# easiri.net
KiCad netlist of a schematic drawn in EAGLE
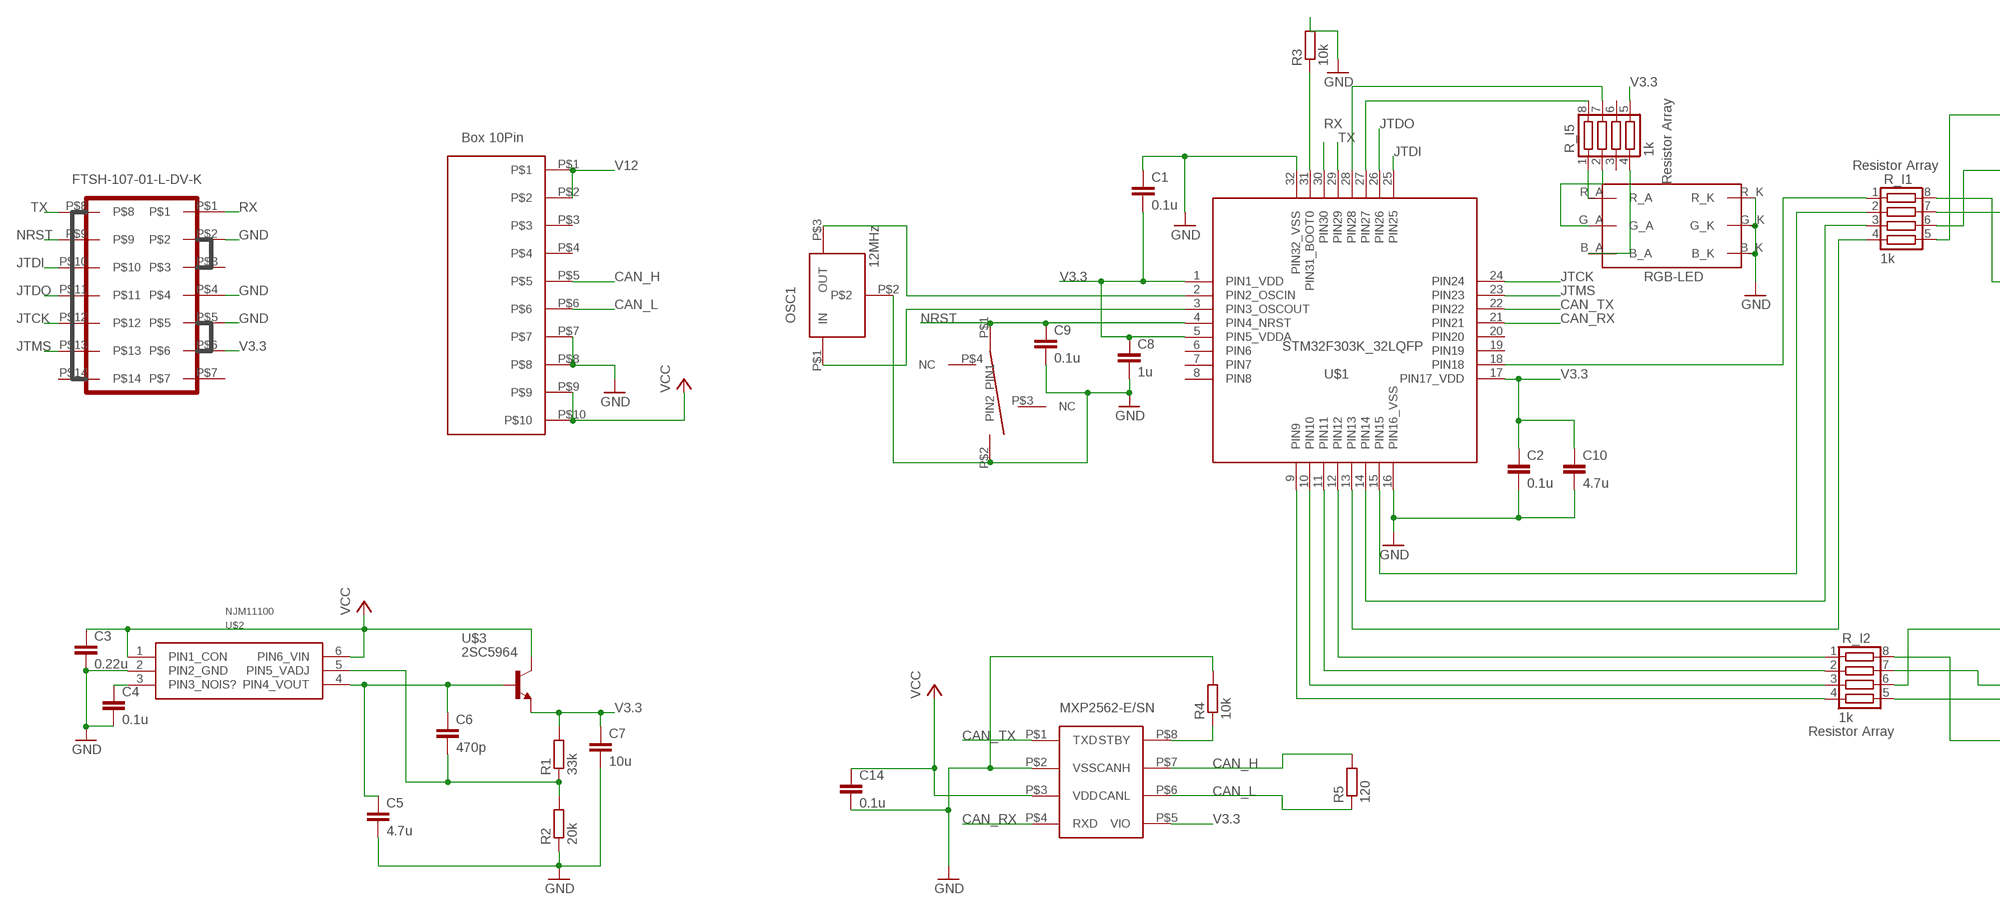
[diagram p0: schematic, sheet 1, part 1 of 2]
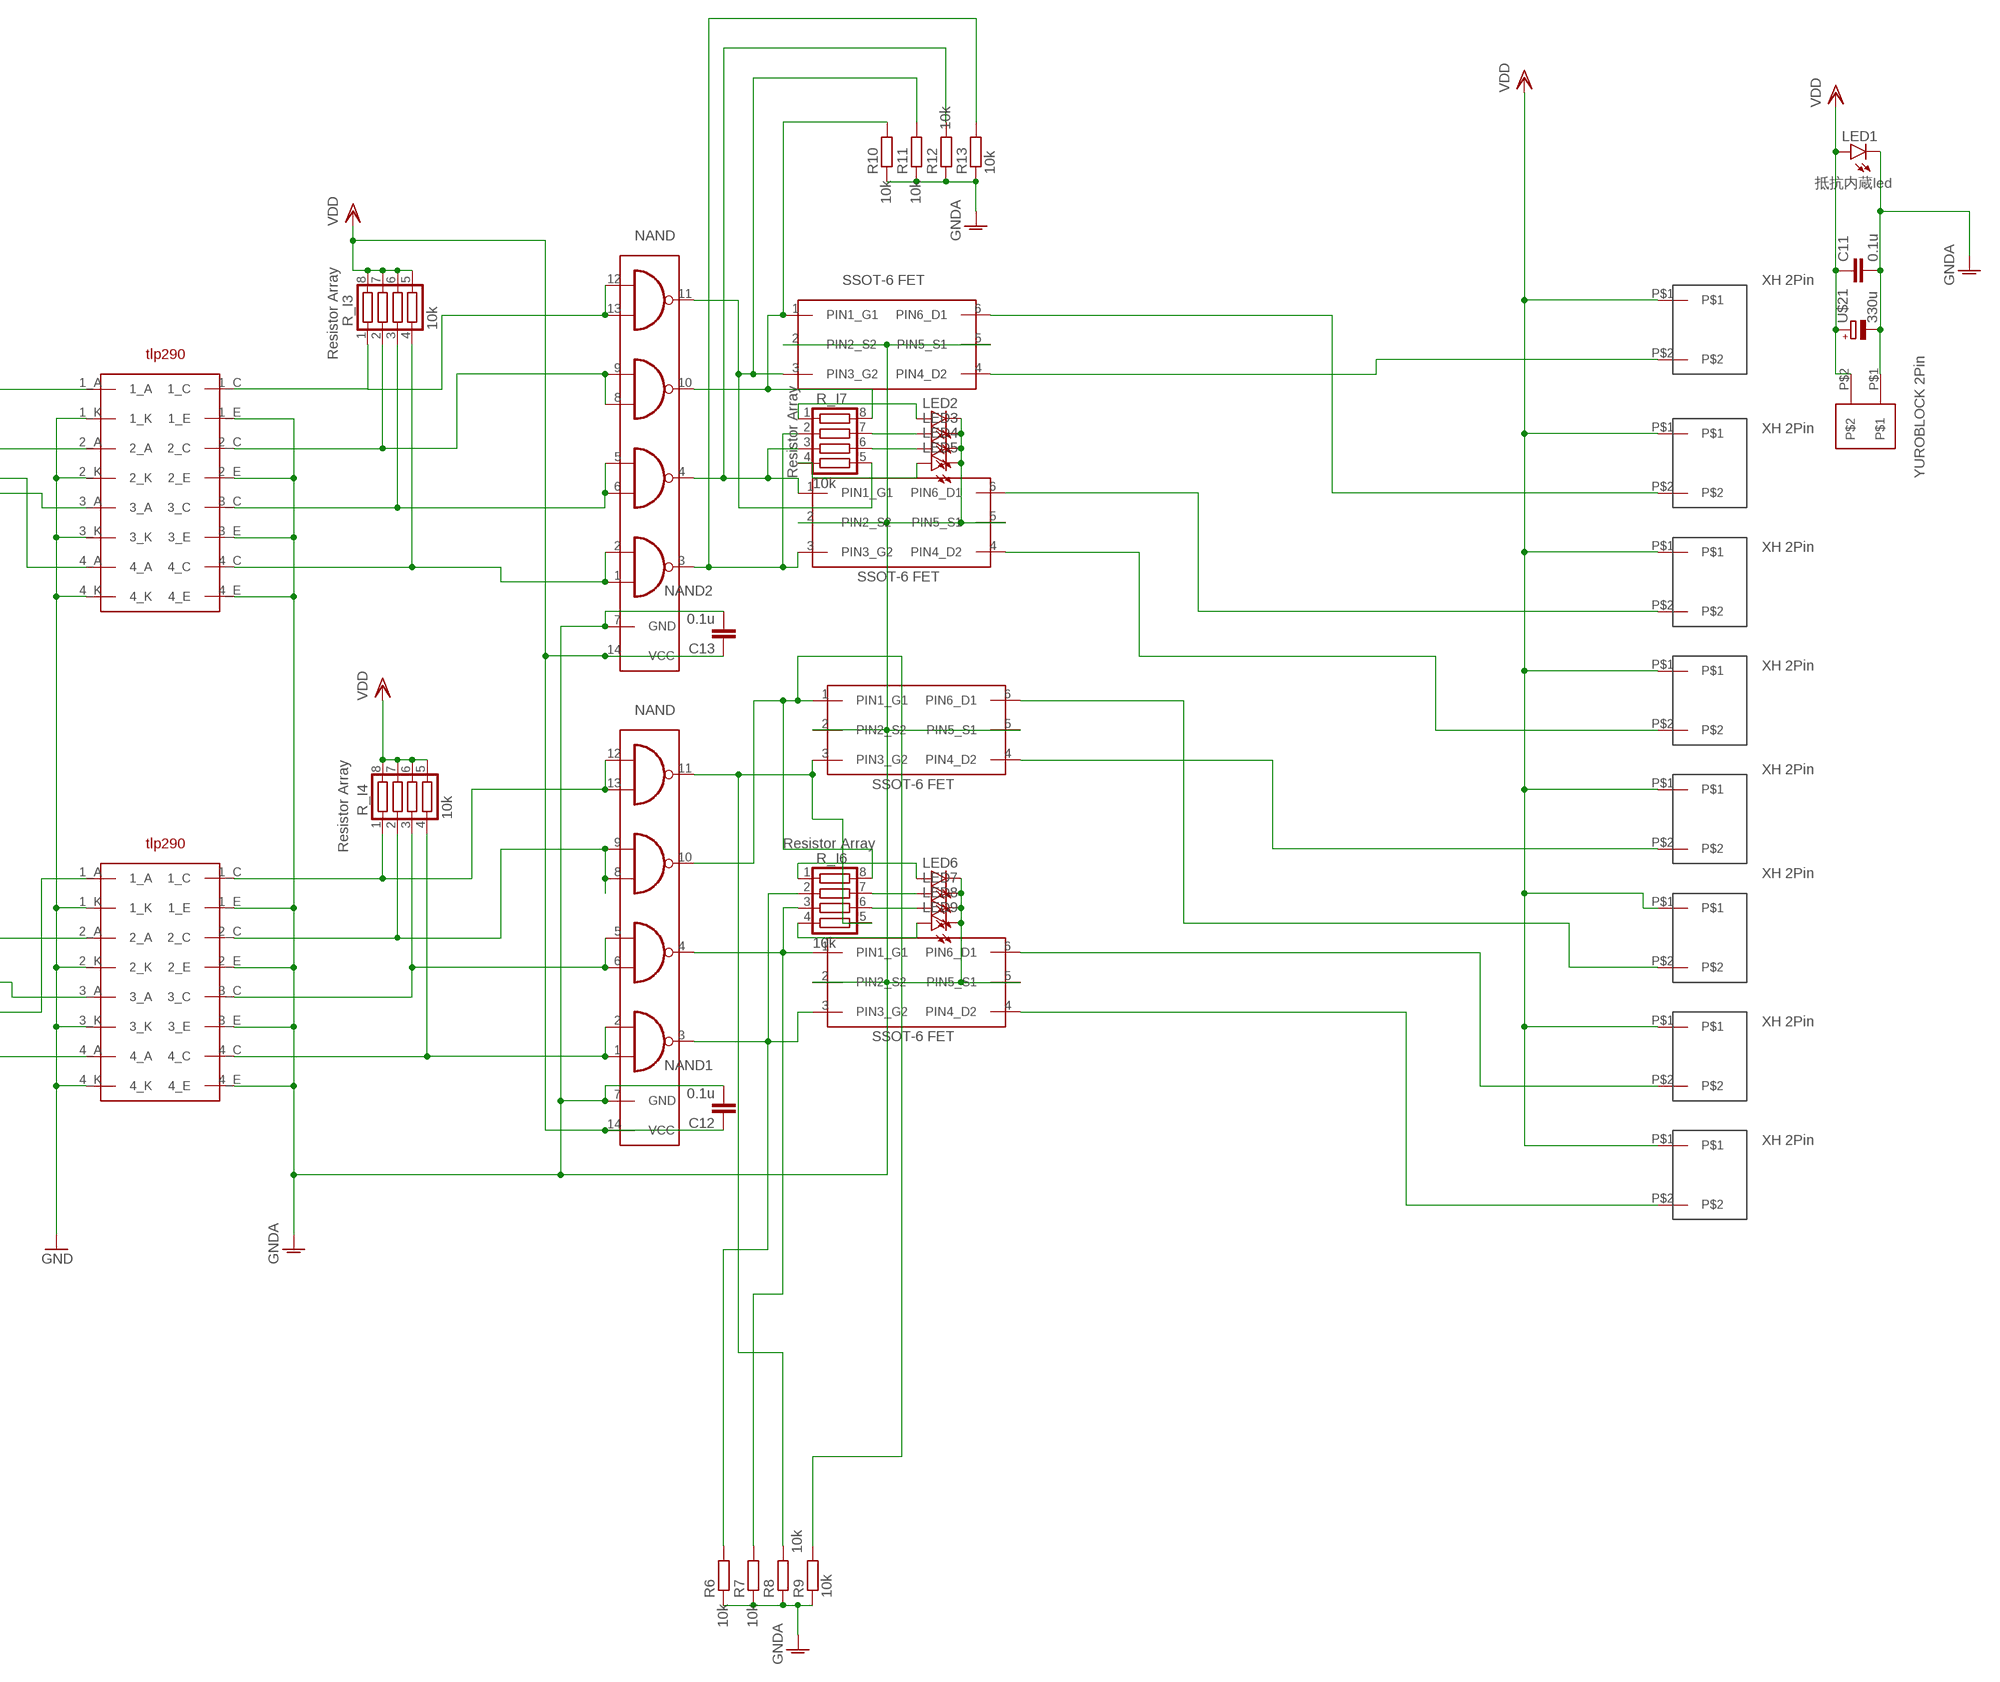
[diagram p1: schematic, sheet 1, part 2 of 2]

(export (version "E")
  (design (tool "Eeschema 10.0.6"))
  (components
    (comp (ref "BOX10P-L2")
      (value "BOX10PBOX10P-L")
      (footprint "eagle-import:BOX10P-L")
      (libsource (lib "eagle-import") (part "BOX10PBOX10P-L"))
    )
    (comp (ref "C1")
      (value "0.1u")
      (footprint "eagle-import:C1608")
      (libsource (lib "eagle-import") (part "C-EUC1608"))
    )
    (comp (ref "C2")
      (value "0.1u")
      (footprint "eagle-import:C1608")
      (libsource (lib "eagle-import") (part "C-EUC1608"))
    )
    (comp (ref "C3")
      (value "0.22u")
      (footprint "eagle-import:C2012")
      (libsource (lib "eagle-import") (part "C-EUC2012"))
    )
    (comp (ref "C4")
      (value "0.1u")
      (footprint "eagle-import:C1608")
      (libsource (lib "eagle-import") (part "C-EUC1608"))
    )
    (comp (ref "C5")
      (value "4.7u")
      (footprint "eagle-import:C2012")
      (libsource (lib "eagle-import") (part "C-EUC2012"))
    )
    (comp (ref "C6")
      (value "470p")
      (footprint "eagle-import:C1608")
      (libsource (lib "eagle-import") (part "C-EUC1608"))
    )
    (comp (ref "C7")
      (value "10u")
      (footprint "eagle-import:C2012")
      (libsource (lib "eagle-import") (part "C-EUC2012"))
    )
    (comp (ref "C8")
      (value "1u")
      (footprint "eagle-import:C1608")
      (libsource (lib "eagle-import") (part "C-EUC1608"))
    )
    (comp (ref "C9")
      (value "0.1u")
      (footprint "eagle-import:C1608")
      (libsource (lib "eagle-import") (part "C-EUC1608"))
    )
    (comp (ref "C10")
      (value "4.7u")
      (footprint "eagle-import:C2012")
      (libsource (lib "eagle-import") (part "C-EUC2012"))
    )
    (comp (ref "C11")
      (value "0.1u")
      (footprint "eagle-import:C1608")
      (libsource (lib "eagle-import") (part "C-EUC1608"))
    )
    (comp (ref "C12")
      (value "0.1u")
      (footprint "eagle-import:C1608")
      (libsource (lib "eagle-import") (part "C-EUC1608"))
    )
    (comp (ref "C13")
      (value "0.1u")
      (footprint "eagle-import:C1608")
      (libsource (lib "eagle-import") (part "C-EUC1608"))
    )
    (comp (ref "C14")
      (value "0.1u")
      (footprint "eagle-import:C1608")
      (libsource (lib "eagle-import") (part "C-EUC1608"))
    )
    (comp (ref "ES1")
      (value "XH_2P")
      (footprint "eagle-import:XH_2P")
      (libsource (lib "eagle-import") (part "XH_2P"))
    )
    (comp (ref "ES2")
      (value "XH_2P")
      (footprint "eagle-import:XH_2P")
      (libsource (lib "eagle-import") (part "XH_2P"))
    )
    (comp (ref "ES3")
      (value "XH_2P")
      (footprint "eagle-import:XH_2P")
      (libsource (lib "eagle-import") (part "XH_2P"))
    )
    (comp (ref "ES4")
      (value "XH_2P")
      (footprint "eagle-import:XH_2P")
      (libsource (lib "eagle-import") (part "XH_2P"))
    )
    (comp (ref "ES5")
      (value "XH_2P")
      (footprint "eagle-import:XH_2P")
      (libsource (lib "eagle-import") (part "XH_2P"))
    )
    (comp (ref "ES6")
      (value "XH_2P")
      (footprint "eagle-import:XH_2P")
      (libsource (lib "eagle-import") (part "XH_2P"))
    )
    (comp (ref "ES7")
      (value "XH_2P")
      (footprint "eagle-import:XH_2P")
      (libsource (lib "eagle-import") (part "XH_2P"))
    )
    (comp (ref "ES8")
      (value "XH_2P")
      (footprint "eagle-import:XH_2P")
      (libsource (lib "eagle-import") (part "XH_2P"))
    )
    (comp (ref "LED1")
      (value "抵抗内蔵led")
      (footprint "eagle-import:LED5MM")
      (libsource (lib "eagle-import") (part "LED5MM"))
    )
    (comp (ref "LED2")
      (value "1608LED")
      (footprint "eagle-import:1608")
      (libsource (lib "eagle-import") (part "1608LED"))
    )
    (comp (ref "LED3")
      (value "1608LED")
      (footprint "eagle-import:1608")
      (libsource (lib "eagle-import") (part "1608LED"))
    )
    (comp (ref "LED4")
      (value "1608LED")
      (footprint "eagle-import:1608")
      (libsource (lib "eagle-import") (part "1608LED"))
    )
    (comp (ref "LED5")
      (value "1608LED")
      (footprint "eagle-import:1608")
      (libsource (lib "eagle-import") (part "1608LED"))
    )
    (comp (ref "LED6")
      (value "1608LED")
      (footprint "eagle-import:1608")
      (libsource (lib "eagle-import") (part "1608LED"))
    )
    (comp (ref "LED7")
      (value "1608LED")
      (footprint "eagle-import:1608")
      (libsource (lib "eagle-import") (part "1608LED"))
    )
    (comp (ref "LED8")
      (value "1608LED")
      (footprint "eagle-import:1608")
      (libsource (lib "eagle-import") (part "1608LED"))
    )
    (comp (ref "LED9")
      (value "1608LED")
      (footprint "eagle-import:1608")
      (libsource (lib "eagle-import") (part "1608LED"))
    )
    (comp (ref "NAND1")
      (value "14PIN_NAND2")
      (footprint "eagle-import:TSSOP14")
      (libsource (lib "eagle-import") (part "14PIN_NAND2"))
    )
    (comp (ref "NAND2")
      (value "14PIN_NAND2")
      (footprint "eagle-import:TSSOP14")
      (libsource (lib "eagle-import") (part "14PIN_NAND2"))
    )
    (comp (ref "OSC1")
      (value "12MHz")
      (footprint "eagle-import:CSTNE#")
      (libsource (lib "eagle-import") (part "CSTN#"))
    )
    (comp (ref "R1")
      (value "33k")
      (footprint "eagle-import:1608")
      (libsource (lib "eagle-import") (part "R_REG"))
    )
    (comp (ref "R2")
      (value "20k")
      (footprint "eagle-import:1608")
      (libsource (lib "eagle-import") (part "R_REG"))
    )
    (comp (ref "R3")
      (value "10k")
      (footprint "eagle-import:1608")
      (libsource (lib "eagle-import") (part "R_REG"))
    )
    (comp (ref "R4")
      (value "10k")
      (footprint "eagle-import:1608")
      (libsource (lib "eagle-import") (part "R_REG"))
    )
    (comp (ref "R5")
      (value "120")
      (footprint "eagle-import:1608")
      (libsource (lib "eagle-import") (part "R_REG"))
    )
    (comp (ref "R6")
      (value "10k")
      (footprint "eagle-import:1608")
      (libsource (lib "eagle-import") (part "R_REG"))
    )
    (comp (ref "R7")
      (value "10k")
      (footprint "eagle-import:1608")
      (libsource (lib "eagle-import") (part "R_REG"))
    )
    (comp (ref "R8")
      (value "10k")
      (footprint "eagle-import:1608")
      (libsource (lib "eagle-import") (part "R_REG"))
    )
    (comp (ref "R9")
      (value "10k")
      (footprint "eagle-import:1608")
      (libsource (lib "eagle-import") (part "R_REG"))
    )
    (comp (ref "R10")
      (value "10k")
      (footprint "eagle-import:1608")
      (libsource (lib "eagle-import") (part "R_REG"))
    )
    (comp (ref "R11")
      (value "10k")
      (footprint "eagle-import:1608")
      (libsource (lib "eagle-import") (part "R_REG"))
    )
    (comp (ref "R12")
      (value "10k")
      (footprint "eagle-import:1608")
      (libsource (lib "eagle-import") (part "R_REG"))
    )
    (comp (ref "R13")
      (value "10k")
      (footprint "eagle-import:1608")
      (libsource (lib "eagle-import") (part "R_REG"))
    )
    (comp (ref "R_I1")
      (value "1k")
      (footprint "eagle-import:0603X4RESISTOR")
      (libsource (lib "eagle-import") (part "R_SHUGOU"))
    )
    (comp (ref "R_I2")
      (value "1k")
      (footprint "eagle-import:0603X4RESISTOR")
      (libsource (lib "eagle-import") (part "R_SHUGOU"))
    )
    (comp (ref "R_I3")
      (value "10k")
      (footprint "eagle-import:1005X4RESISTOR")
      (libsource (lib "eagle-import") (part "R_SHUGOU2"))
    )
    (comp (ref "R_I4")
      (value "10k")
      (footprint "eagle-import:1005X4RESISTOR")
      (libsource (lib "eagle-import") (part "R_SHUGOU2"))
    )
    (comp (ref "R_I5")
      (value "1k")
      (footprint "eagle-import:0603X4RESISTOR")
      (libsource (lib "eagle-import") (part "R_SHUGOU"))
    )
    (comp (ref "R_I6")
      (value "10k")
      (footprint "eagle-import:1005X4RESISTOR")
      (libsource (lib "eagle-import") (part "R_SHUGOU2"))
    )
    (comp (ref "R_I7")
      (value "10k")
      (footprint "eagle-import:1005X4RESISTOR")
      (libsource (lib "eagle-import") (part "R_SHUGOU2"))
    )
    (comp (ref "U$1")
      (value "STM32F303K_32LQFP")
      (footprint "eagle-import:LQFP32-7X7")
      (libsource (lib "eagle-import") (part "STM32F303K_32LQFP"))
    )
    (comp (ref "U$2")
      (value "NJM11100")
      (footprint "eagle-import:SOT23-6")
      (libsource (lib "eagle-import") (part "NJM11100"))
    )
    (comp (ref "U$3")
      (value "2SC5964")
      (footprint "eagle-import:PCP")
      (libsource (lib "eagle-import") (part "2SC5964"))
    )
    (comp (ref "U$4")
      (value "TAKUTOSUITTI2")
      (footprint "eagle-import:TAKUTOSUITTI2")
      (libsource (lib "eagle-import") (part "TAKUTOSUITTI2"))
    )
    (comp (ref "U$5")
      (value "MCP2562MCP2561-SN")
      (footprint "eagle-import:SOIC8")
      (libsource (lib "eagle-import") (part "MCP2562MCP2561-SN"))
    )
    (comp (ref "U$6")
      (value "TLP290-4")
      (footprint "eagle-import:TLP290")
      (libsource (lib "eagle-import") (part "TLP290-4"))
    )
    (comp (ref "U$7")
      (value "TLP290-4")
      (footprint "eagle-import:TLP290")
      (libsource (lib "eagle-import") (part "TLP290-4"))
    )
    (comp (ref "U$8")
      (value "SSOT6_FET")
      (footprint "eagle-import:SSOT6")
      (libsource (lib "eagle-import") (part "SSOT6_FET"))
    )
    (comp (ref "U$9")
      (value "SSOT6_FET")
      (footprint "eagle-import:SSOT6")
      (libsource (lib "eagle-import") (part "SSOT6_FET"))
    )
    (comp (ref "U$10")
      (value "SSOT6_FET")
      (footprint "eagle-import:SSOT6")
      (libsource (lib "eagle-import") (part "SSOT6_FET"))
    )
    (comp (ref "U$11")
      (value "SSOT6_FET")
      (footprint "eagle-import:SSOT6")
      (libsource (lib "eagle-import") (part "SSOT6_FET"))
    )
    (comp (ref "U$12")
      (value "YUROBLOCK2")
      (footprint "eagle-import:YUROBLOCK2")
      (libsource (lib "eagle-import") (part "YUROBLOCK2"))
    )
    (comp (ref "U$13")
      (value "FTSH-107-01-L-DV-K")
      (footprint "eagle-import:FTSH-107-01-L-DV-K")
      (libsource (lib "eagle-import") (part "FTSH-107-01-L-DV-K"))
    )
    (comp (ref "U$21")
      (value "330u")
      (footprint "eagle-import:1014CAPA")
      (libsource (lib "eagle-import") (part "C_DEKAI"))
    )
    (comp (ref "U$23")
      (value "RGB_LED")
      (footprint "eagle-import:RGB_LED")
      (libsource (lib "eagle-import") (part "RGB_LED"))
    )
  )
  (nets
    (net (code "1") (name "/CAN_H") (class "Default")
      (node (ref "BOX10P-L2") (pin "P$5") (pinfunction "P$5_P$5") (pintype "bidirectional"))
      (node (ref "R5") (pin "2") (pinfunction "2_2") (pintype "passive"))
      (node (ref "U$5") (pin "P$7") (pinfunction "CANH_P$7") (pintype "bidirectional"))
    )
    (net (code "2") (name "/CAN_L") (class "Default")
      (node (ref "BOX10P-L2") (pin "P$6") (pinfunction "P$6_P$6") (pintype "bidirectional"))
      (node (ref "R5") (pin "1") (pinfunction "1_1") (pintype "passive"))
      (node (ref "U$5") (pin "P$6") (pinfunction "CANL_P$6") (pintype "bidirectional"))
    )
    (net (code "3") (name "/CAN_RX") (class "Default")
      (node (ref "U$1") (pin "21") (pinfunction "PIN21_21") (pintype "bidirectional"))
      (node (ref "U$5") (pin "P$4") (pinfunction "RXD_P$4") (pintype "bidirectional"))
    )
    (net (code "4") (name "/CAN_TX") (class "Default")
      (node (ref "U$1") (pin "22") (pinfunction "PIN22_22") (pintype "bidirectional"))
      (node (ref "U$5") (pin "P$1") (pinfunction "TXD_P$1") (pintype "bidirectional"))
    )
    (net (code "5") (name "/JTCK") (class "Default")
      (node (ref "U$1") (pin "24") (pinfunction "PIN24_24") (pintype "bidirectional"))
      (node (ref "U$13") (pin "P$12") (pinfunction "P$12_P$12") (pintype "bidirectional"))
    )
    (net (code "6") (name "/JTDI") (class "Default")
      (node (ref "U$1") (pin "25") (pinfunction "PIN25_25") (pintype "bidirectional"))
      (node (ref "U$13") (pin "P$10") (pinfunction "P$10_P$10") (pintype "bidirectional"))
    )
    (net (code "7") (name "/JTDO") (class "Default")
      (node (ref "U$1") (pin "26") (pinfunction "PIN26_26") (pintype "bidirectional"))
      (node (ref "U$13") (pin "P$11") (pinfunction "P$11_P$11") (pintype "bidirectional"))
    )
    (net (code "8") (name "/JTMS") (class "Default")
      (node (ref "U$1") (pin "23") (pinfunction "PIN23_23") (pintype "bidirectional"))
      (node (ref "U$13") (pin "P$13") (pinfunction "P$13_P$13") (pintype "bidirectional"))
    )
    (net (code "9") (name "/NRST") (class "Default")
      (node (ref "C9") (pin "1") (pinfunction "1_1") (pintype "passive"))
      (node (ref "U$1") (pin "4") (pinfunction "PIN4_NRST_4") (pintype "bidirectional"))
      (node (ref "U$13") (pin "P$9") (pinfunction "P$9_P$9") (pintype "bidirectional"))
      (node (ref "U$4") (pin "P$1") (pinfunction "PIN1_P$1") (pintype "bidirectional"))
    )
    (net (code "10") (name "/RX") (class "Default")
      (node (ref "U$1") (pin "30") (pinfunction "PIN30_30") (pintype "bidirectional"))
      (node (ref "U$13") (pin "P$1") (pinfunction "P$1_P$1") (pintype "bidirectional"))
    )
    (net (code "11") (name "/TX") (class "Default")
      (node (ref "U$1") (pin "29") (pinfunction "PIN29_29") (pintype "bidirectional"))
      (node (ref "U$13") (pin "P$8") (pinfunction "P$8_P$8") (pintype "bidirectional"))
    )
    (net (code "12") (name "/V3.3") (class "Default")
      (node (ref "C1") (pin "2") (pinfunction "2_2") (pintype "passive"))
      (node (ref "C10") (pin "1") (pinfunction "1_1") (pintype "passive"))
      (node (ref "C2") (pin "1") (pinfunction "1_1") (pintype "passive"))
      (node (ref "C7") (pin "1") (pinfunction "1_1") (pintype "passive"))
      (node (ref "C8") (pin "1") (pinfunction "1_1") (pintype "passive"))
      (node (ref "R1") (pin "2") (pinfunction "2_2") (pintype "passive"))
      (node (ref "R_I5") (pin "5") (pinfunction "5_5") (pintype "passive"))
      (node (ref "U$1") (pin "1") (pinfunction "PIN1_VDD_1") (pintype "bidirectional"))
      (node (ref "U$1") (pin "17") (pinfunction "PIN17_VDD_17") (pintype "bidirectional"))
      (node (ref "U$1") (pin "5") (pinfunction "PIN5_VDDA_5") (pintype "bidirectional"))
      (node (ref "U$13") (pin "P$6") (pinfunction "P$6_P$6") (pintype "bidirectional"))
      (node (ref "U$3") (pin "3") (pinfunction "E_3") (pintype "passive"))
      (node (ref "U$5") (pin "P$5") (pinfunction "VIO_P$5") (pintype "bidirectional"))
    )
    (net (code "13") (name "/V12") (class "Default")
      (node (ref "BOX10P-L2") (pin "P$1") (pinfunction "P$1_P$1") (pintype "bidirectional"))
      (node (ref "BOX10P-L2") (pin "P$2") (pinfunction "P$2_P$2") (pintype "bidirectional"))
    )
    (net (code "14") (name "GND") (class "Default")
      (node (ref "BOX10P-L2") (pin "P$7") (pinfunction "P$7_P$7") (pintype "bidirectional"))
      (node (ref "BOX10P-L2") (pin "P$8") (pinfunction "P$8_P$8") (pintype "bidirectional"))
      (node (ref "C1") (pin "1") (pinfunction "1_1") (pintype "passive"))
      (node (ref "C10") (pin "2") (pinfunction "2_2") (pintype "passive"))
      (node (ref "C14") (pin "2") (pinfunction "2_2") (pintype "passive"))
      (node (ref "C2") (pin "2") (pinfunction "2_2") (pintype "passive"))
      (node (ref "C3") (pin "2") (pinfunction "2_2") (pintype "passive"))
      (node (ref "C4") (pin "2") (pinfunction "2_2") (pintype "passive"))
      (node (ref "C5") (pin "2") (pinfunction "2_2") (pintype "passive"))
      (node (ref "C7") (pin "2") (pinfunction "2_2") (pintype "passive"))
      (node (ref "C8") (pin "2") (pinfunction "2_2") (pintype "passive"))
      (node (ref "C9") (pin "2") (pinfunction "2_2") (pintype "passive"))
      (node (ref "OSC1") (pin "P$2") (pinfunction "P$2_P$2") (pintype "bidirectional"))
      (node (ref "R2") (pin "1") (pinfunction "1_1") (pintype "passive"))
      (node (ref "R3") (pin "2") (pinfunction "2_2") (pintype "passive"))
      (node (ref "R4") (pin "2") (pinfunction "2_2") (pintype "passive"))
      (node (ref "U$1") (pin "16") (pinfunction "PIN16_VSS_16") (pintype "bidirectional"))
      (node (ref "U$1") (pin "32") (pinfunction "PIN32_VSS_32") (pintype "bidirectional"))
      (node (ref "U$13") (pin "P$2") (pinfunction "P$2_P$2") (pintype "bidirectional"))
      (node (ref "U$13") (pin "P$4") (pinfunction "P$4_P$4") (pintype "bidirectional"))
      (node (ref "U$13") (pin "P$5") (pinfunction "P$5_P$5") (pintype "bidirectional"))
      (node (ref "U$2") (pin "2") (pinfunction "PIN2_GND_2") (pintype "bidirectional"))
      (node (ref "U$23") (pin "B_K") (pinfunction "B_K_B_K") (pintype "bidirectional"))
      (node (ref "U$23") (pin "G_K") (pinfunction "G_K_G_K") (pintype "bidirectional"))
      (node (ref "U$23") (pin "R_K") (pinfunction "R_K_R_K") (pintype "bidirectional"))
      (node (ref "U$4") (pin "P$2") (pinfunction "PIN2_P$2") (pintype "bidirectional"))
      (node (ref "U$5") (pin "P$2") (pinfunction "VSS_P$2") (pintype "bidirectional"))
      (node (ref "U$6") (pin "1_K") (pinfunction "1_K_1_K") (pintype "bidirectional"))
      (node (ref "U$6") (pin "2_K") (pinfunction "2_K_2_K") (pintype "bidirectional"))
      (node (ref "U$6") (pin "3_K") (pinfunction "3_K_3_K") (pintype "bidirectional"))
      (node (ref "U$6") (pin "4_K") (pinfunction "4_K_4_K") (pintype "bidirectional"))
      (node (ref "U$7") (pin "1_K") (pinfunction "1_K_1_K") (pintype "bidirectional"))
      (node (ref "U$7") (pin "2_K") (pinfunction "2_K_2_K") (pintype "bidirectional"))
      (node (ref "U$7") (pin "3_K") (pinfunction "3_K_3_K") (pintype "bidirectional"))
      (node (ref "U$7") (pin "4_K") (pinfunction "4_K_4_K") (pintype "bidirectional"))
    )
    (net (code "15") (name "GNDA") (class "Default")
      (node (ref "C11") (pin "2") (pinfunction "2_2") (pintype "passive"))
      (node (ref "C12") (pin "2") (pinfunction "2_2") (pintype "passive"))
      (node (ref "C13") (pin "2") (pinfunction "2_2") (pintype "passive"))
      (node (ref "LED1") (pin "K") (pinfunction "C_K") (pintype "passive"))
      (node (ref "LED2") (pin "K") (pinfunction "K_K") (pintype "passive"))
      (node (ref "LED3") (pin "K") (pinfunction "K_K") (pintype "passive"))
      (node (ref "LED4") (pin "K") (pinfunction "K_K") (pintype "passive"))
      (node (ref "LED5") (pin "K") (pinfunction "K_K") (pintype "passive"))
      (node (ref "LED6") (pin "K") (pinfunction "K_K") (pintype "passive"))
      (node (ref "LED7") (pin "K") (pinfunction "K_K") (pintype "passive"))
      (node (ref "LED8") (pin "K") (pinfunction "K_K") (pintype "passive"))
      (node (ref "LED9") (pin "K") (pinfunction "K_K") (pintype "passive"))
      (node (ref "NAND1") (pin "7") (pinfunction "GND_7") (pintype "bidirectional"))
      (node (ref "NAND2") (pin "7") (pinfunction "GND_7") (pintype "bidirectional"))
      (node (ref "R10") (pin "1") (pinfunction "1_1") (pintype "passive"))
      (node (ref "R11") (pin "1") (pinfunction "1_1") (pintype "passive"))
      (node (ref "R12") (pin "1") (pinfunction "1_1") (pintype "passive"))
      (node (ref "R13") (pin "1") (pinfunction "1_1") (pintype "passive"))
      (node (ref "R6") (pin "1") (pinfunction "1_1") (pintype "passive"))
      (node (ref "R7") (pin "1") (pinfunction "1_1") (pintype "passive"))
      (node (ref "R8") (pin "1") (pinfunction "1_1") (pintype "passive"))
      (node (ref "R9") (pin "1") (pinfunction "1_1") (pintype "passive"))
      (node (ref "U$10") (pin "2") (pinfunction "PIN2_S2_2") (pintype "bidirectional"))
      (node (ref "U$10") (pin "5") (pinfunction "PIN5_S1_5") (pintype "bidirectional"))
      (node (ref "U$11") (pin "2") (pinfunction "PIN2_S2_2") (pintype "bidirectional"))
      (node (ref "U$11") (pin "5") (pinfunction "PIN5_S1_5") (pintype "bidirectional"))
      (node (ref "U$12") (pin "P$1") (pinfunction "P$1_P$1") (pintype "bidirectional"))
      (node (ref "U$21") (pin "-") (pinfunction "-_-") (pintype "passive"))
      (node (ref "U$6") (pin "1_E") (pinfunction "1_E_1_E") (pintype "bidirectional"))
      (node (ref "U$6") (pin "2_E") (pinfunction "2_E_2_E") (pintype "bidirectional"))
      (node (ref "U$6") (pin "3_E") (pinfunction "3_E_3_E") (pintype "bidirectional"))
      (node (ref "U$6") (pin "4_E") (pinfunction "4_E_4_E") (pintype "bidirectional"))
      (node (ref "U$7") (pin "1_E") (pinfunction "1_E_1_E") (pintype "bidirectional"))
      (node (ref "U$7") (pin "2_E") (pinfunction "2_E_2_E") (pintype "bidirectional"))
      (node (ref "U$7") (pin "3_E") (pinfunction "3_E_3_E") (pintype "bidirectional"))
      (node (ref "U$7") (pin "4_E") (pinfunction "4_E_4_E") (pintype "bidirectional"))
      (node (ref "U$8") (pin "2") (pinfunction "PIN2_S2_2") (pintype "bidirectional"))
      (node (ref "U$8") (pin "5") (pinfunction "PIN5_S1_5") (pintype "bidirectional"))
      (node (ref "U$9") (pin "2") (pinfunction "PIN2_S2_2") (pintype "bidirectional"))
      (node (ref "U$9") (pin "5") (pinfunction "PIN5_S1_5") (pintype "bidirectional"))
    )
    (net (code "16") (name "Net-(LED2-PadA)") (class "Default")
      (node (ref "LED2") (pin "A") (pinfunction "A_A") (pintype "passive"))
      (node (ref "R_I7") (pin "1") (pinfunction "1_1") (pintype "passive"))
    )
    (net (code "17") (name "Net-(LED3-PadA)") (class "Default")
      (node (ref "LED3") (pin "A") (pinfunction "A_A") (pintype "passive"))
      (node (ref "R_I7") (pin "7") (pinfunction "7_7") (pintype "passive"))
    )
    (net (code "18") (name "Net-(LED4-PadA)") (class "Default")
      (node (ref "LED4") (pin "A") (pinfunction "A_A") (pintype "passive"))
      (node (ref "R_I7") (pin "6") (pinfunction "6_6") (pintype "passive"))
    )
    (net (code "19") (name "Net-(LED5-PadA)") (class "Default")
      (node (ref "LED5") (pin "A") (pinfunction "A_A") (pintype "passive"))
      (node (ref "R_I7") (pin "4") (pinfunction "4_4") (pintype "passive"))
    )
    (net (code "20") (name "Net-(LED6-PadA)") (class "Default")
      (node (ref "LED6") (pin "A") (pinfunction "A_A") (pintype "passive"))
      (node (ref "R_I6") (pin "1") (pinfunction "1_1") (pintype "passive"))
    )
    (net (code "21") (name "Net-(LED7-PadA)") (class "Default")
      (node (ref "LED7") (pin "A") (pinfunction "A_A") (pintype "passive"))
      (node (ref "R_I6") (pin "7") (pinfunction "7_7") (pintype "passive"))
    )
    (net (code "22") (name "Net-(LED8-PadA)") (class "Default")
      (node (ref "LED8") (pin "A") (pinfunction "A_A") (pintype "passive"))
      (node (ref "R_I6") (pin "6") (pinfunction "6_6") (pintype "passive"))
    )
    (net (code "23") (name "Net-(LED9-PadA)") (class "Default")
      (node (ref "LED9") (pin "A") (pinfunction "A_A") (pintype "passive"))
      (node (ref "R_I6") (pin "4") (pinfunction "4_4") (pintype "passive"))
    )
    (net (code "24") (name "Net-(NAND1-1A)") (class "Default")
      (node (ref "NAND1") (pin "1") (pinfunction "1A_1") (pintype "input"))
      (node (ref "NAND1") (pin "2") (pinfunction "1B_2") (pintype "input"))
      (node (ref "R_I4") (pin "4") (pinfunction "4_4") (pintype "passive"))
      (node (ref "U$7") (pin "4_C") (pinfunction "4_C_4_C") (pintype "bidirectional"))
    )
    (net (code "25") (name "Net-(NAND1-1Y)") (class "Default")
      (node (ref "NAND1") (pin "3") (pinfunction "1Y_3") (pintype "output"))
      (node (ref "R6") (pin "2") (pinfunction "2_2") (pintype "passive"))
      (node (ref "R_I6") (pin "2") (pinfunction "2_2") (pintype "passive"))
      (node (ref "U$11") (pin "3") (pinfunction "PIN3_G2_3") (pintype "bidirectional"))
    )
    (net (code "26") (name "Net-(NAND1-2A)") (class "Default")
      (node (ref "NAND1") (pin "5") (pinfunction "2B_5") (pintype "input"))
      (node (ref "NAND1") (pin "6") (pinfunction "2A_6") (pintype "input"))
      (node (ref "R_I4") (pin "3") (pinfunction "3_3") (pintype "passive"))
      (node (ref "U$7") (pin "3_C") (pinfunction "3_C_3_C") (pintype "bidirectional"))
    )
    (net (code "27") (name "Net-(NAND1-2Y)") (class "Default")
      (node (ref "NAND1") (pin "4") (pinfunction "2Y_4") (pintype "output"))
      (node (ref "R7") (pin "2") (pinfunction "2_2") (pintype "passive"))
      (node (ref "R_I6") (pin "3") (pinfunction "3_3") (pintype "passive"))
      (node (ref "U$11") (pin "1") (pinfunction "PIN1_G1_1") (pintype "bidirectional"))
    )
    (net (code "28") (name "Net-(NAND1-3A)") (class "Default")
      (node (ref "NAND1") (pin "8") (pinfunction "3A_8") (pintype "input"))
      (node (ref "NAND1") (pin "9") (pinfunction "3B_9") (pintype "input"))
      (node (ref "R_I4") (pin "2") (pinfunction "2_2") (pintype "passive"))
      (node (ref "U$7") (pin "2_C") (pinfunction "2_C_2_C") (pintype "bidirectional"))
    )
    (net (code "29") (name "Net-(NAND1-3Y)") (class "Default")
      (node (ref "NAND1") (pin "10") (pinfunction "3Y_10") (pintype "output"))
      (node (ref "R9") (pin "2") (pinfunction "2_2") (pintype "passive"))
      (node (ref "R_I6") (pin "8") (pinfunction "8_8") (pintype "passive"))
      (node (ref "U$10") (pin "1") (pinfunction "PIN1_G1_1") (pintype "bidirectional"))
    )
    (net (code "30") (name "Net-(NAND1-4A)") (class "Default")
      (node (ref "NAND1") (pin "12") (pinfunction "4B_12") (pintype "input"))
      (node (ref "NAND1") (pin "13") (pinfunction "4A_13") (pintype "input"))
      (node (ref "R_I4") (pin "1") (pinfunction "1_1") (pintype "passive"))
      (node (ref "U$7") (pin "1_C") (pinfunction "1_C_1_C") (pintype "bidirectional"))
    )
    (net (code "31") (name "Net-(NAND1-4Y)") (class "Default")
      (node (ref "NAND1") (pin "11") (pinfunction "4Y_11") (pintype "output"))
      (node (ref "R8") (pin "2") (pinfunction "2_2") (pintype "passive"))
      (node (ref "R_I6") (pin "5") (pinfunction "5_5") (pintype "passive"))
      (node (ref "U$10") (pin "3") (pinfunction "PIN3_G2_3") (pintype "bidirectional"))
    )
    (net (code "32") (name "Net-(NAND2-1A)") (class "Default")
      (node (ref "NAND2") (pin "1") (pinfunction "1A_1") (pintype "input"))
      (node (ref "NAND2") (pin "2") (pinfunction "1B_2") (pintype "input"))
      (node (ref "R_I3") (pin "4") (pinfunction "4_4") (pintype "passive"))
      (node (ref "U$6") (pin "4_C") (pinfunction "4_C_4_C") (pintype "bidirectional"))
    )
    (net (code "33") (name "Net-(NAND2-1Y)") (class "Default")
      (node (ref "NAND2") (pin "3") (pinfunction "1Y_3") (pintype "output"))
      (node (ref "R13") (pin "2") (pinfunction "2_2") (pintype "passive"))
      (node (ref "R_I7") (pin "2") (pinfunction "2_2") (pintype "passive"))
      (node (ref "U$9") (pin "3") (pinfunction "PIN3_G2_3") (pintype "bidirectional"))
    )
    (net (code "34") (name "Net-(NAND2-2A)") (class "Default")
      (node (ref "NAND2") (pin "5") (pinfunction "2B_5") (pintype "input"))
      (node (ref "NAND2") (pin "6") (pinfunction "2A_6") (pintype "input"))
      (node (ref "R_I3") (pin "3") (pinfunction "3_3") (pintype "passive"))
      (node (ref "U$6") (pin "3_C") (pinfunction "3_C_3_C") (pintype "bidirectional"))
    )
    (net (code "35") (name "Net-(NAND2-2Y)") (class "Default")
      (node (ref "NAND2") (pin "4") (pinfunction "2Y_4") (pintype "output"))
      (node (ref "R12") (pin "2") (pinfunction "2_2") (pintype "passive"))
      (node (ref "R_I7") (pin "3") (pinfunction "3_3") (pintype "passive"))
      (node (ref "U$9") (pin "1") (pinfunction "PIN1_G1_1") (pintype "bidirectional"))
    )
    (net (code "36") (name "Net-(NAND2-3A)") (class "Default")
      (node (ref "NAND2") (pin "8") (pinfunction "3A_8") (pintype "input"))
      (node (ref "NAND2") (pin "9") (pinfunction "3B_9") (pintype "input"))
      (node (ref "R_I3") (pin "2") (pinfunction "2_2") (pintype "passive"))
      (node (ref "U$6") (pin "2_C") (pinfunction "2_C_2_C") (pintype "bidirectional"))
    )
    (net (code "37") (name "Net-(NAND2-3Y)") (class "Default")
      (node (ref "NAND2") (pin "10") (pinfunction "3Y_10") (pintype "output"))
      (node (ref "R10") (pin "2") (pinfunction "2_2") (pintype "passive"))
      (node (ref "R_I7") (pin "8") (pinfunction "8_8") (pintype "passive"))
      (node (ref "U$8") (pin "1") (pinfunction "PIN1_G1_1") (pintype "bidirectional"))
    )
    (net (code "38") (name "Net-(NAND2-4A)") (class "Default")
      (node (ref "NAND2") (pin "12") (pinfunction "4B_12") (pintype "input"))
      (node (ref "NAND2") (pin "13") (pinfunction "4A_13") (pintype "input"))
      (node (ref "R_I3") (pin "1") (pinfunction "1_1") (pintype "passive"))
      (node (ref "U$6") (pin "1_C") (pinfunction "1_C_1_C") (pintype "bidirectional"))
    )
    (net (code "39") (name "Net-(NAND2-4Y)") (class "Default")
      (node (ref "NAND2") (pin "11") (pinfunction "4Y_11") (pintype "output"))
      (node (ref "R11") (pin "2") (pinfunction "2_2") (pintype "passive"))
      (node (ref "R_I7") (pin "5") (pinfunction "5_5") (pintype "passive"))
      (node (ref "U$8") (pin "3") (pinfunction "PIN3_G2_3") (pintype "bidirectional"))
    )
    (net (code "40") (name "Net-(OSC1-IN)") (class "Default")
      (node (ref "OSC1") (pin "P$1") (pinfunction "IN_P$1") (pintype "bidirectional"))
      (node (ref "U$1") (pin "3") (pinfunction "PIN3_OSCOUT_3") (pintype "bidirectional"))
    )
    (net (code "41") (name "Net-(OSC1-OUT)") (class "Default")
      (node (ref "OSC1") (pin "P$3") (pinfunction "OUT_P$3") (pintype "bidirectional"))
      (node (ref "U$1") (pin "2") (pinfunction "PIN2_OSCIN_2") (pintype "bidirectional"))
    )
    (net (code "42") (name "Net-(R_I1-Pad5)") (class "Default")
      (node (ref "R_I1") (pin "5") (pinfunction "5_5") (pintype "passive"))
      (node (ref "U$6") (pin "1_A") (pinfunction "1_A_1_A") (pintype "bidirectional"))
    )
    (net (code "43") (name "Net-(R_I1-Pad6)") (class "Default")
      (node (ref "R_I1") (pin "6") (pinfunction "6_6") (pintype "passive"))
      (node (ref "U$6") (pin "2_A") (pinfunction "2_A_2_A") (pintype "bidirectional"))
    )
    (net (code "44") (name "Net-(R_I1-Pad7)") (class "Default")
      (node (ref "R_I1") (pin "7") (pinfunction "7_7") (pintype "passive"))
      (node (ref "U$6") (pin "3_A") (pinfunction "3_A_3_A") (pintype "bidirectional"))
    )
    (net (code "45") (name "Net-(R_I1-Pad8)") (class "Default")
      (node (ref "R_I1") (pin "8") (pinfunction "8_8") (pintype "passive"))
      (node (ref "U$6") (pin "4_A") (pinfunction "4_A_4_A") (pintype "bidirectional"))
    )
    (net (code "46") (name "Net-(R_I2-Pad5)") (class "Default")
      (node (ref "R_I2") (pin "5") (pinfunction "5_5") (pintype "passive"))
      (node (ref "U$7") (pin "1_A") (pinfunction "1_A_1_A") (pintype "bidirectional"))
    )
    (net (code "47") (name "Net-(R_I2-Pad6)") (class "Default")
      (node (ref "R_I2") (pin "6") (pinfunction "6_6") (pintype "passive"))
      (node (ref "U$7") (pin "2_A") (pinfunction "2_A_2_A") (pintype "bidirectional"))
    )
    (net (code "48") (name "Net-(R_I2-Pad7)") (class "Default")
      (node (ref "R_I2") (pin "7") (pinfunction "7_7") (pintype "passive"))
      (node (ref "U$7") (pin "3_A") (pinfunction "3_A_3_A") (pintype "bidirectional"))
    )
    (net (code "49") (name "Net-(R_I2-Pad8)") (class "Default")
      (node (ref "R_I2") (pin "8") (pinfunction "8_8") (pintype "passive"))
      (node (ref "U$7") (pin "4_A") (pinfunction "4_A_4_A") (pintype "bidirectional"))
    )
    (net (code "50") (name "Net-(R_I5-Pad1)") (class "Default")
      (node (ref "R_I5") (pin "1") (pinfunction "1_1") (pintype "passive"))
      (node (ref "U$23") (pin "R_A") (pinfunction "R_A_R_A") (pintype "bidirectional"))
    )
    (net (code "51") (name "Net-(R_I5-Pad2)") (class "Default")
      (node (ref "R_I5") (pin "2") (pinfunction "2_2") (pintype "passive"))
      (node (ref "U$23") (pin "G_A") (pinfunction "G_A_G_A") (pintype "bidirectional"))
    )
    (net (code "52") (name "Net-(R_I5-Pad4)") (class "Default")
      (node (ref "R_I5") (pin "4") (pinfunction "4_4") (pintype "passive"))
      (node (ref "U$23") (pin "B_A") (pinfunction "B_A_B_A") (pintype "bidirectional"))
    )
    (net (code "53") (name "Net-(U$1-PIN9)") (class "Default")
      (node (ref "R_I2") (pin "4") (pinfunction "4_4") (pintype "passive"))
      (node (ref "U$1") (pin "9") (pinfunction "PIN9_9") (pintype "bidirectional"))
    )
    (net (code "54") (name "Net-(U$1-PIN10)") (class "Default")
      (node (ref "R_I2") (pin "3") (pinfunction "3_3") (pintype "passive"))
      (node (ref "U$1") (pin "10") (pinfunction "PIN10_10") (pintype "bidirectional"))
    )
    (net (code "55") (name "Net-(U$1-PIN11)") (class "Default")
      (node (ref "R_I2") (pin "2") (pinfunction "2_2") (pintype "passive"))
      (node (ref "U$1") (pin "11") (pinfunction "PIN11_11") (pintype "bidirectional"))
    )
    (net (code "56") (name "Net-(U$1-PIN12)") (class "Default")
      (node (ref "R_I2") (pin "1") (pinfunction "1_1") (pintype "passive"))
      (node (ref "U$1") (pin "12") (pinfunction "PIN12_12") (pintype "bidirectional"))
    )
    (net (code "57") (name "Net-(U$1-PIN13)") (class "Default")
      (node (ref "R_I1") (pin "4") (pinfunction "4_4") (pintype "passive"))
      (node (ref "U$1") (pin "13") (pinfunction "PIN13_13") (pintype "bidirectional"))
    )
    (net (code "58") (name "Net-(U$1-PIN14)") (class "Default")
      (node (ref "R_I1") (pin "3") (pinfunction "3_3") (pintype "passive"))
      (node (ref "U$1") (pin "14") (pinfunction "PIN14_14") (pintype "bidirectional"))
    )
    (net (code "59") (name "Net-(U$1-PIN15)") (class "Default")
      (node (ref "R_I1") (pin "2") (pinfunction "2_2") (pintype "passive"))
      (node (ref "U$1") (pin "15") (pinfunction "PIN15_15") (pintype "bidirectional"))
    )
    (net (code "60") (name "Net-(U$1-PIN18)") (class "Default")
      (node (ref "R_I1") (pin "1") (pinfunction "1_1") (pintype "passive"))
      (node (ref "U$1") (pin "18") (pinfunction "PIN18_18") (pintype "bidirectional"))
    )
    (net (code "61") (name "Net-(U$1-PIN27)") (class "Default")
      (node (ref "R_I5") (pin "8") (pinfunction "8_8") (pintype "passive"))
      (node (ref "U$1") (pin "27") (pinfunction "PIN27_27") (pintype "bidirectional"))
    )
    (net (code "62") (name "Net-(U$1-PIN28)") (class "Default")
      (node (ref "R_I5") (pin "7") (pinfunction "7_7") (pintype "passive"))
      (node (ref "U$1") (pin "28") (pinfunction "PIN28_28") (pintype "bidirectional"))
    )
    (net (code "63") (name "Net-(U$1-PIN31_BOOT0)") (class "Default")
      (node (ref "R3") (pin "1") (pinfunction "1_1") (pintype "passive"))
      (node (ref "U$1") (pin "31") (pinfunction "PIN31_BOOT0_31") (pintype "bidirectional"))
    )
    (net (code "64") (name "Net-(U$2-PIN3_NOIS?)") (class "Default")
      (node (ref "C4") (pin "1") (pinfunction "1_1") (pintype "passive"))
      (node (ref "U$2") (pin "3") (pinfunction "PIN3_NOIS?_3") (pintype "bidirectional"))
    )
    (net (code "65") (name "Net-(U$2-PIN4_VOUT)") (class "Default")
      (node (ref "C5") (pin "1") (pinfunction "1_1") (pintype "passive"))
      (node (ref "C6") (pin "1") (pinfunction "1_1") (pintype "passive"))
      (node (ref "U$2") (pin "4") (pinfunction "PIN4_VOUT_4") (pintype "bidirectional"))
      (node (ref "U$3") (pin "1") (pinfunction "B_1") (pintype "passive"))
    )
    (net (code "66") (name "Net-(U$2-PIN5_VADJ)") (class "Default")
      (node (ref "C6") (pin "2") (pinfunction "2_2") (pintype "passive"))
      (node (ref "R1") (pin "1") (pinfunction "1_1") (pintype "passive"))
      (node (ref "R2") (pin "2") (pinfunction "2_2") (pintype "passive"))
      (node (ref "U$2") (pin "5") (pinfunction "PIN5_VADJ_5") (pintype "bidirectional"))
    )
    (net (code "67") (name "Net-(U$5-STBY)") (class "Default")
      (node (ref "R4") (pin "1") (pinfunction "1_1") (pintype "passive"))
      (node (ref "U$5") (pin "P$8") (pinfunction "STBY_P$8") (pintype "bidirectional"))
    )
    (net (code "68") (name "Net-(U$8-PIN4_D2)") (class "Default")
      (node (ref "ES1") (pin "P$2") (pinfunction "P$2_P$2") (pintype "bidirectional"))
      (node (ref "U$8") (pin "4") (pinfunction "PIN4_D2_4") (pintype "bidirectional"))
    )
    (net (code "69") (name "Net-(U$8-PIN6_D1)") (class "Default")
      (node (ref "ES2") (pin "P$2") (pinfunction "P$2_P$2") (pintype "bidirectional"))
      (node (ref "U$8") (pin "6") (pinfunction "PIN6_D1_6") (pintype "bidirectional"))
    )
    (net (code "70") (name "Net-(U$9-PIN4_D2)") (class "Default")
      (node (ref "ES4") (pin "P$2") (pinfunction "P$2_P$2") (pintype "bidirectional"))
      (node (ref "U$9") (pin "4") (pinfunction "PIN4_D2_4") (pintype "bidirectional"))
    )
    (net (code "71") (name "Net-(U$9-PIN6_D1)") (class "Default")
      (node (ref "ES3") (pin "P$2") (pinfunction "P$2_P$2") (pintype "bidirectional"))
      (node (ref "U$9") (pin "6") (pinfunction "PIN6_D1_6") (pintype "bidirectional"))
    )
    (net (code "72") (name "Net-(U$10-PIN4_D2)") (class "Default")
      (node (ref "ES5") (pin "P$2") (pinfunction "P$2_P$2") (pintype "bidirectional"))
      (node (ref "U$10") (pin "4") (pinfunction "PIN4_D2_4") (pintype "bidirectional"))
    )
    (net (code "73") (name "Net-(U$10-PIN6_D1)") (class "Default")
      (node (ref "ES6") (pin "P$2") (pinfunction "P$2_P$2") (pintype "bidirectional"))
      (node (ref "U$10") (pin "6") (pinfunction "PIN6_D1_6") (pintype "bidirectional"))
    )
    (net (code "74") (name "Net-(U$11-PIN4_D2)") (class "Default")
      (node (ref "ES8") (pin "P$2") (pinfunction "P$2_P$2") (pintype "bidirectional"))
      (node (ref "U$11") (pin "4") (pinfunction "PIN4_D2_4") (pintype "bidirectional"))
    )
    (net (code "75") (name "Net-(U$11-PIN6_D1)") (class "Default")
      (node (ref "ES7") (pin "P$2") (pinfunction "P$2_P$2") (pintype "bidirectional"))
      (node (ref "U$11") (pin "6") (pinfunction "PIN6_D1_6") (pintype "bidirectional"))
    )
    (net (code "76") (name "VCC") (class "Default")
      (node (ref "BOX10P-L2") (pin "P$10") (pinfunction "P$10_P$10") (pintype "bidirectional"))
      (node (ref "BOX10P-L2") (pin "P$9") (pinfunction "P$9_P$9") (pintype "bidirectional"))
      (node (ref "C14") (pin "1") (pinfunction "1_1") (pintype "passive"))
      (node (ref "C3") (pin "1") (pinfunction "1_1") (pintype "passive"))
      (node (ref "U$2") (pin "1") (pinfunction "PIN1_CON_1") (pintype "bidirectional"))
      (node (ref "U$2") (pin "6") (pinfunction "PIN6_VIN_6") (pintype "bidirectional"))
      (node (ref "U$3") (pin "2") (pinfunction "C_2") (pintype "passive"))
      (node (ref "U$3") (pin "2@2") (pinfunction "C_2@2") (pintype "passive"))
      (node (ref "U$5") (pin "P$3") (pinfunction "VDD_P$3") (pintype "bidirectional"))
    )
    (net (code "77") (name "VDD") (class "Default")
      (node (ref "C11") (pin "1") (pinfunction "1_1") (pintype "passive"))
      (node (ref "C12") (pin "1") (pinfunction "1_1") (pintype "passive"))
      (node (ref "C13") (pin "1") (pinfunction "1_1") (pintype "passive"))
      (node (ref "ES1") (pin "P$1") (pinfunction "P$1_P$1") (pintype "bidirectional"))
      (node (ref "ES2") (pin "P$1") (pinfunction "P$1_P$1") (pintype "bidirectional"))
      (node (ref "ES3") (pin "P$1") (pinfunction "P$1_P$1") (pintype "bidirectional"))
      (node (ref "ES4") (pin "P$1") (pinfunction "P$1_P$1") (pintype "bidirectional"))
      (node (ref "ES5") (pin "P$1") (pinfunction "P$1_P$1") (pintype "bidirectional"))
      (node (ref "ES6") (pin "P$1") (pinfunction "P$1_P$1") (pintype "bidirectional"))
      (node (ref "ES7") (pin "P$1") (pinfunction "P$1_P$1") (pintype "bidirectional"))
      (node (ref "ES8") (pin "P$1") (pinfunction "P$1_P$1") (pintype "bidirectional"))
      (node (ref "LED1") (pin "A") (pinfunction "A_A") (pintype "passive"))
      (node (ref "NAND1") (pin "14") (pinfunction "VCC_14") (pintype "bidirectional"))
      (node (ref "NAND2") (pin "14") (pinfunction "VCC_14") (pintype "bidirectional"))
      (node (ref "R_I3") (pin "5") (pinfunction "5_5") (pintype "passive"))
      (node (ref "R_I3") (pin "6") (pinfunction "6_6") (pintype "passive"))
      (node (ref "R_I3") (pin "7") (pinfunction "7_7") (pintype "passive"))
      (node (ref "R_I3") (pin "8") (pinfunction "8_8") (pintype "passive"))
      (node (ref "R_I4") (pin "5") (pinfunction "5_5") (pintype "passive"))
      (node (ref "R_I4") (pin "6") (pinfunction "6_6") (pintype "passive"))
      (node (ref "R_I4") (pin "7") (pinfunction "7_7") (pintype "passive"))
      (node (ref "R_I4") (pin "8") (pinfunction "8_8") (pintype "passive"))
      (node (ref "U$12") (pin "P$2") (pinfunction "P$2_P$2") (pintype "bidirectional"))
      (node (ref "U$21") (pin "+") (pinfunction "+_+") (pintype "passive"))
    )
    (net (code "78") (name "unconnected-(BOX10P-L2-PadP$3)") (class "Default")
      (node (ref "BOX10P-L2") (pin "P$3") (pinfunction "P$3_P$3") (pintype "bidirectional"))
    )
    (net (code "79") (name "unconnected-(BOX10P-L2-PadP$4)") (class "Default")
      (node (ref "BOX10P-L2") (pin "P$4") (pinfunction "P$4_P$4") (pintype "bidirectional"))
    )
    (net (code "80") (name "unconnected-(R_I5-Pad3)") (class "Default")
      (node (ref "R_I5") (pin "3") (pinfunction "3_3") (pintype "passive"))
    )
    (net (code "81") (name "unconnected-(R_I5-Pad6)") (class "Default")
      (node (ref "R_I5") (pin "6") (pinfunction "6_6") (pintype "passive"))
    )
    (net (code "82") (name "unconnected-(U$1-PIN6-Pad6)") (class "Default")
      (node (ref "U$1") (pin "6") (pinfunction "PIN6_6") (pintype "bidirectional"))
    )
    (net (code "83") (name "unconnected-(U$1-PIN7-Pad7)") (class "Default")
      (node (ref "U$1") (pin "7") (pinfunction "PIN7_7") (pintype "bidirectional"))
    )
    (net (code "84") (name "unconnected-(U$1-PIN8-Pad8)") (class "Default")
      (node (ref "U$1") (pin "8") (pinfunction "PIN8_8") (pintype "bidirectional"))
    )
    (net (code "85") (name "unconnected-(U$1-PIN19-Pad19)") (class "Default")
      (node (ref "U$1") (pin "19") (pinfunction "PIN19_19") (pintype "bidirectional"))
    )
    (net (code "86") (name "unconnected-(U$1-PIN20-Pad20)") (class "Default")
      (node (ref "U$1") (pin "20") (pinfunction "PIN20_20") (pintype "bidirectional"))
    )
    (net (code "87") (name "unconnected-(U$4-NC-PadP$3)") (class "Default")
      (node (ref "U$4") (pin "P$3") (pinfunction "NC_P$3") (pintype "bidirectional"))
    )
    (net (code "88") (name "unconnected-(U$4-NC-PadP$4)") (class "Default")
      (node (ref "U$4") (pin "P$4") (pinfunction "NC_P$4") (pintype "bidirectional"))
    )
    (net (code "89") (name "unconnected-(U$13-PadP$3)") (class "Default")
      (node (ref "U$13") (pin "P$3") (pinfunction "P$3_P$3") (pintype "bidirectional"))
    )
    (net (code "90") (name "unconnected-(U$13-PadP$7)") (class "Default")
      (node (ref "U$13") (pin "P$7") (pinfunction "P$7_P$7") (pintype "bidirectional"))
    )
    (net (code "91") (name "unconnected-(U$13-PadP$14)") (class "Default")
      (node (ref "U$13") (pin "P$14") (pinfunction "P$14_P$14") (pintype "bidirectional"))
    )
  )
)
